# blue_pot_proto.net
KiCad netlist of a schematic drawn in EAGLE
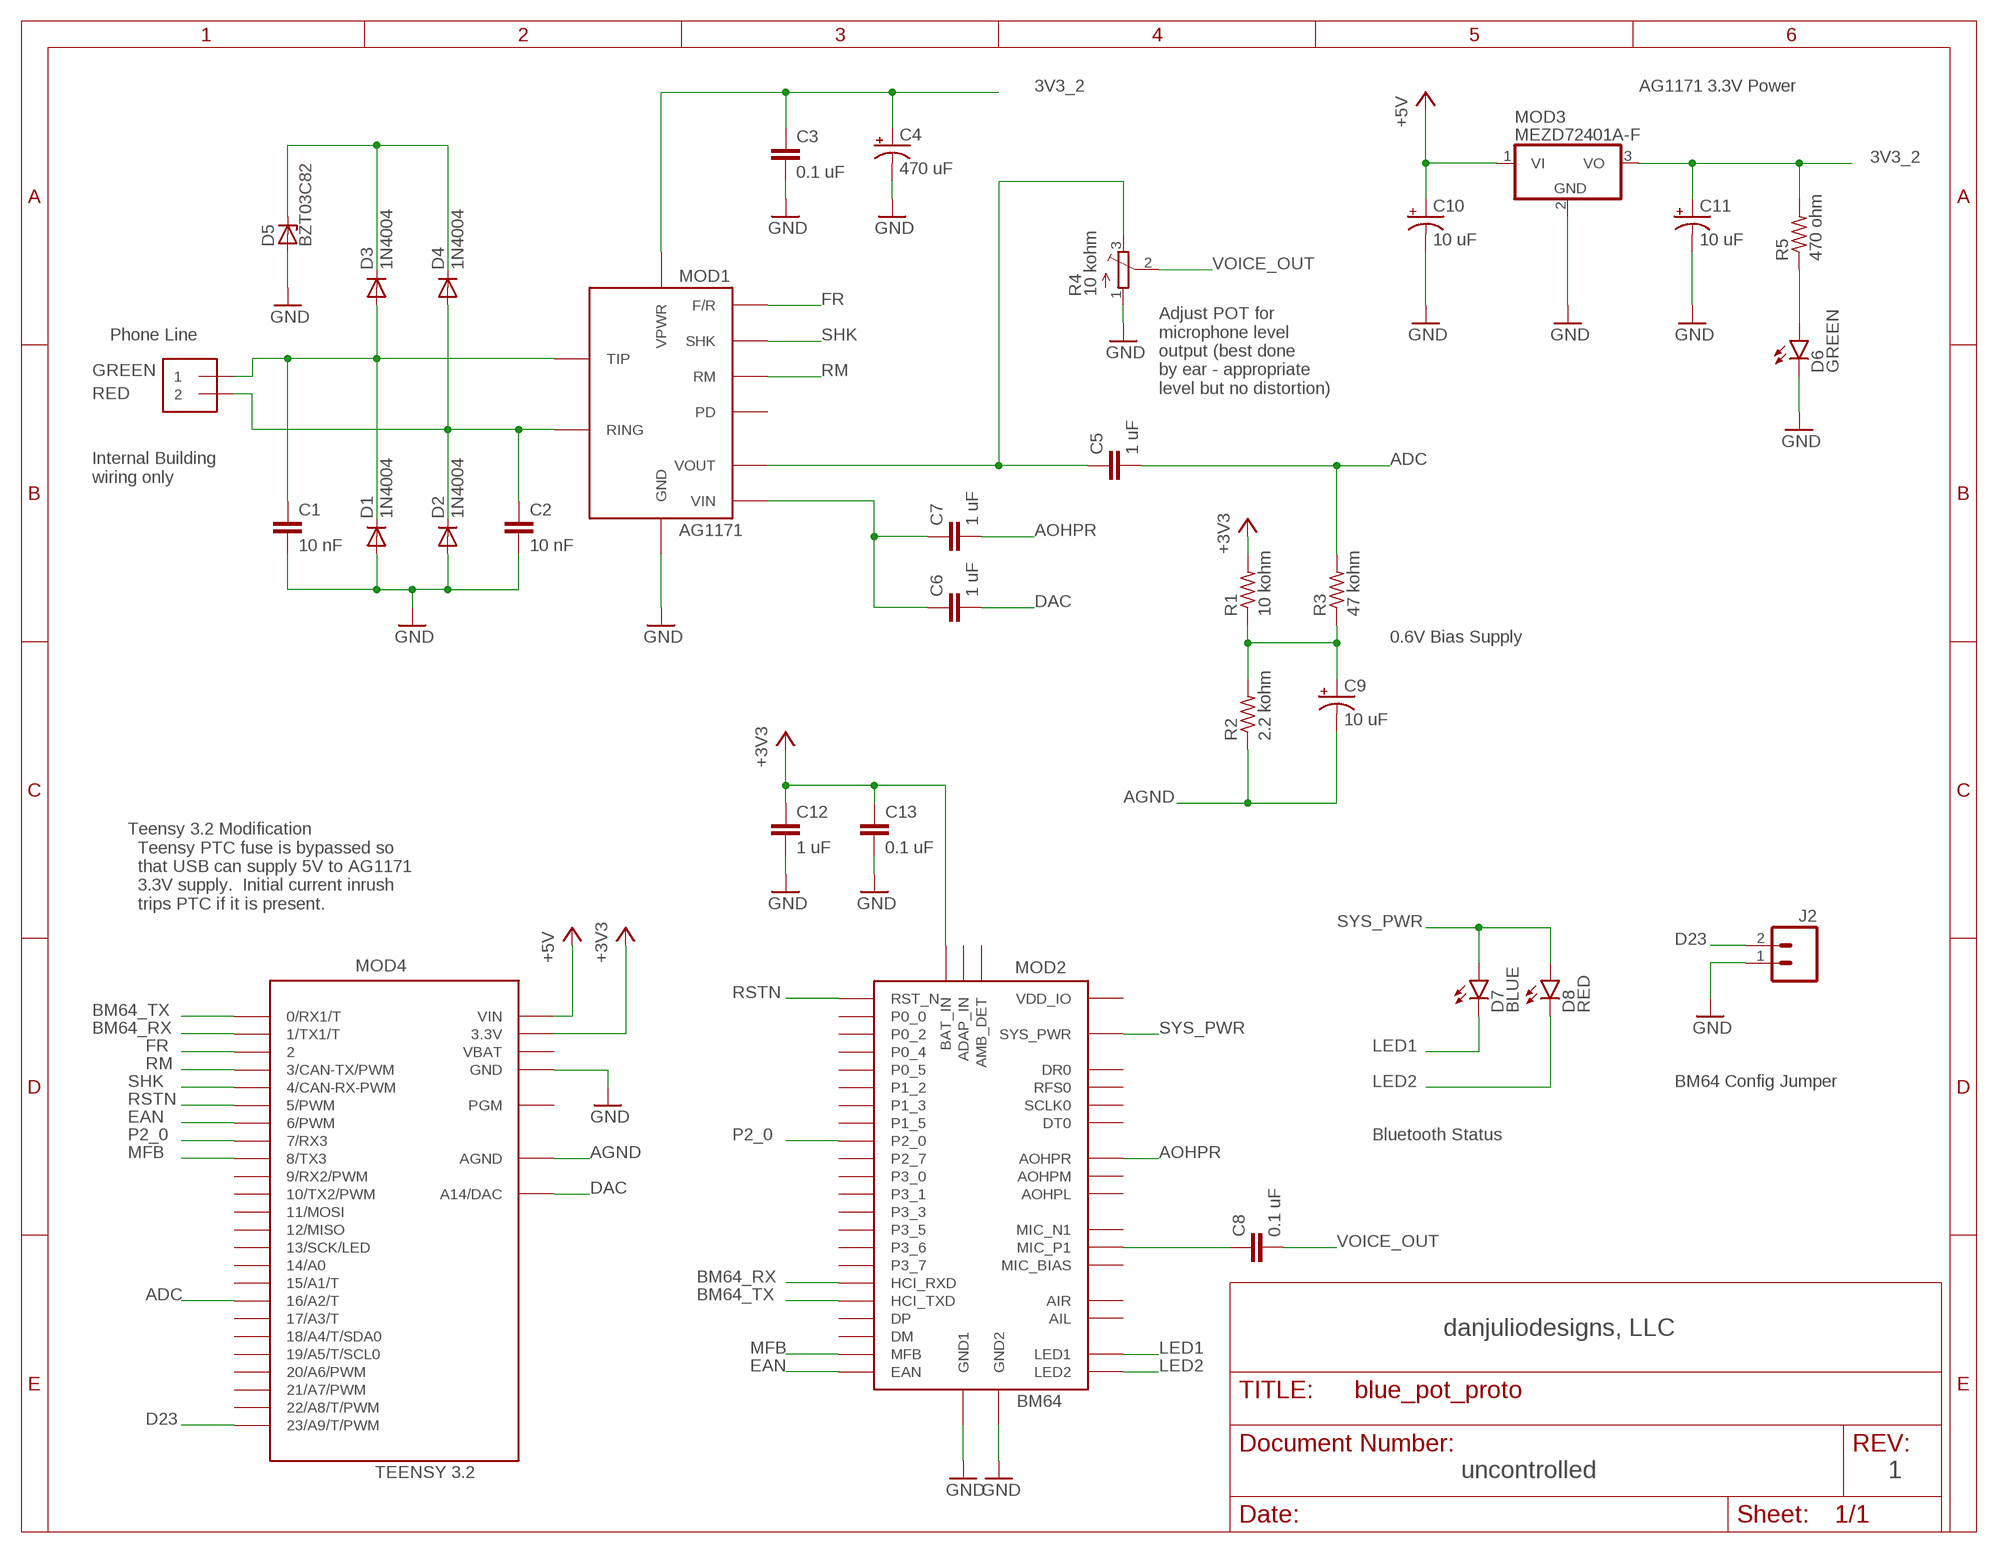
[diagram p0: schematic, sheet 1]

(export (version "E")
  (design (tool "Eeschema 10.0.6"))
  (components
    (comp (ref "C1")
      (value "10 nF")
      (footprint "eagle-import:C5B2.5")
      (libsource (lib "eagle-import") (part "C5/2.5"))
    )
    (comp (ref "C2")
      (value "10 nF")
      (footprint "eagle-import:C5B2.5")
      (libsource (lib "eagle-import") (part "C5/2.5"))
    )
    (comp (ref "C3")
      (value "0.1 uF")
      (footprint "eagle-import:C5B2.5")
      (libsource (lib "eagle-import") (part "C5/2.5"))
    )
    (comp (ref "C4")
      (value "470 uF")
      (footprint "eagle-import:TT5D10")
      (libsource (lib "eagle-import") (part "CPOL-USTT5D10"))
    )
    (comp (ref "C5")
      (value "1 uF")
      (footprint "eagle-import:C5B2.5")
      (libsource (lib "eagle-import") (part "C5/2.5"))
    )
    (comp (ref "C6")
      (value "1 uF")
      (footprint "eagle-import:C5B2.5")
      (libsource (lib "eagle-import") (part "C5/2.5"))
    )
    (comp (ref "C7")
      (value "1 uF")
      (footprint "eagle-import:C5B2.5")
      (libsource (lib "eagle-import") (part "C5/2.5"))
    )
    (comp (ref "C8")
      (value "0.1 uF")
      (footprint "eagle-import:C5B2.5")
      (libsource (lib "eagle-import") (part "C5/2.5"))
    )
    (comp (ref "C9")
      (value "10 uF")
      (footprint "eagle-import:TT2D5")
      (libsource (lib "eagle-import") (part "CPOL-USTT2D5"))
    )
    (comp (ref "C10")
      (value "10 uF")
      (footprint "eagle-import:TT2D5")
      (libsource (lib "eagle-import") (part "CPOL-USTT2D5"))
    )
    (comp (ref "C11")
      (value "10 uF")
      (footprint "eagle-import:TT2D5")
      (libsource (lib "eagle-import") (part "CPOL-USTT2D5"))
    )
    (comp (ref "C12")
      (value "1 uF")
      (footprint "eagle-import:C5B2.5")
      (libsource (lib "eagle-import") (part "C5/2.5"))
    )
    (comp (ref "C13")
      (value "0.1 uF")
      (footprint "eagle-import:C5B2.5")
      (libsource (lib "eagle-import") (part "C5/2.5"))
    )
    (comp (ref "D1")
      (value "1N4004")
      (footprint "eagle-import:DO41-10")
      (libsource (lib "eagle-import") (part "1N4004"))
    )
    (comp (ref "D2")
      (value "1N4004")
      (footprint "eagle-import:DO41-10")
      (libsource (lib "eagle-import") (part "1N4004"))
    )
    (comp (ref "D3")
      (value "1N4004")
      (footprint "eagle-import:DO41-10")
      (libsource (lib "eagle-import") (part "1N4004"))
    )
    (comp (ref "D4")
      (value "1N4004")
      (footprint "eagle-import:DO41-10")
      (libsource (lib "eagle-import") (part "1N4004"))
    )
    (comp (ref "D5")
      (value "BZT03C82")
      (footprint "eagle-import:SOD57Z10")
      (libsource (lib "eagle-import") (part "BZT03XX"))
    )
    (comp (ref "D6")
      (value "GREEN")
      (footprint "eagle-import:LED5MM")
      (libsource (lib "eagle-import") (part "LED5MM"))
    )
    (comp (ref "D7")
      (value "BLUE")
      (footprint "eagle-import:LED5MM")
      (libsource (lib "eagle-import") (part "LED5MM"))
    )
    (comp (ref "D8")
      (value "RED")
      (footprint "eagle-import:LED5MM")
      (libsource (lib "eagle-import") (part "LED5MM"))
    )
    (comp (ref "J1")
      (value "1X2-3.5MM")
      (footprint "eagle-import:1X2-3.5MM")
      (libsource (lib "eagle-import") (part "1X2-3.5MM"))
    )
    (comp (ref "J2")
      (value "M02PTH")
      (footprint "eagle-import:1X02")
      (libsource (lib "eagle-import") (part "M02PTH"))
    )
    (comp (ref "MOD1")
      (value "AG1171")
      (footprint "eagle-import:AG1171")
      (libsource (lib "eagle-import") (part "AG1171SIL"))
    )
    (comp (ref "MOD2")
      (value "BM64")
      (footprint "eagle-import:BM64")
      (libsource (lib "eagle-import") (part "BM64"))
    )
    (comp (ref "MOD3")
      (value "MEZD72401A-F")
      (footprint "eagle-import:TO220H")
      (libsource (lib "eagle-import") (part "78T05"))
    )
    (comp (ref "MOD4")
      (value "TEENSY 3.2")
      (footprint "eagle-import:TEENSY_3.0-3.2&LC_OUTER_ROW")
      (libsource (lib "eagle-import") (part "TEENSY_3.1-3.2_OUTER_ROW"))
    )
    (comp (ref "R1")
      (value "10 kohm")
      (footprint "eagle-import:0207_10")
      (libsource (lib "eagle-import") (part "R-US_0207/10"))
    )
    (comp (ref "R2")
      (value "2.2 kohm")
      (footprint "eagle-import:0207_10")
      (libsource (lib "eagle-import") (part "R-US_0207/10"))
    )
    (comp (ref "R3")
      (value "47 kohm")
      (footprint "eagle-import:0207_10")
      (libsource (lib "eagle-import") (part "R-US_0207/10"))
    )
    (comp (ref "R4")
      (value "10 kohm")
      (footprint "eagle-import:TC33X")
      (libsource (lib "eagle-import") (part "TRIMPOTTC33X"))
    )
    (comp (ref "R5")
      (value "470 ohm")
      (footprint "eagle-import:0207_10")
      (libsource (lib "eagle-import") (part "R-US_0207/10"))
    )
  )
  (nets
    (net (code "1") (name "+3V3") (class "Default")
      (node (ref "C12") (pin "1") (pinfunction "1_1") (pintype "passive"))
      (node (ref "C13") (pin "1") (pinfunction "1_1") (pintype "passive"))
      (node (ref "MOD2") (pin "22") (pinfunction "BAT_IN_22") (pintype "power_in"))
      (node (ref "MOD4") (pin "3.3V") (pinfunction "3.3V_3.3V") (pintype "power_in"))
      (node (ref "MOD4") (pin "3.3V1") (pinfunction "3.3V_3.3V1") (pintype "power_in"))
      (node (ref "R1") (pin "2") (pinfunction "2_2") (pintype "passive"))
    )
    (net (code "2") (name "+5V") (class "Default")
      (node (ref "C10") (pin "+") (pinfunction "+_+") (pintype "passive"))
      (node (ref "MOD3") (pin "1") (pinfunction "VI_1") (pintype "input"))
      (node (ref "MOD4") (pin "VIN") (pinfunction "VIN_VIN") (pintype "power_in"))
    )
    (net (code "3") (name "/3V3_2") (class "Default")
      (node (ref "C11") (pin "+") (pinfunction "+_+") (pintype "passive"))
      (node (ref "C3") (pin "1") (pinfunction "1_1") (pintype "passive"))
      (node (ref "C4") (pin "+") (pinfunction "+_+") (pintype "passive"))
      (node (ref "MOD1") (pin "P$13") (pinfunction "VPWR_P$13") (pintype "power_in"))
      (node (ref "MOD3") (pin "3") (pinfunction "VO_3") (pintype "passive"))
    )
    (net (code "4") (name "/ADAP_IN") (class "Default")
      (node (ref "MOD2") (pin "23") (pinfunction "ADAP_IN_23") (pintype "power_in"))
    )
    (net (code "5") (name "/ADC") (class "Default")
      (node (ref "C5") (pin "2") (pinfunction "2_2") (pintype "passive"))
      (node (ref "MOD4") (pin "16/A2") (pinfunction "16/A2/T_16/A2") (pintype "bidirectional"))
      (node (ref "R3") (pin "2") (pinfunction "2_2") (pintype "passive"))
    )
    (net (code "6") (name "/AGND") (class "Default")
      (node (ref "C9") (pin "-") (pinfunction "-_-") (pintype "passive"))
      (node (ref "MOD4") (pin "AGND") (pinfunction "AGND_AGND") (pintype "power_in"))
      (node (ref "R2") (pin "1") (pinfunction "1_1") (pintype "passive"))
    )
    (net (code "7") (name "/AOHPR") (class "Default")
      (node (ref "C7") (pin "2") (pinfunction "2_2") (pintype "passive"))
      (node (ref "MOD2") (pin "5") (pinfunction "AOHPR_5") (pintype "passive"))
    )
    (net (code "8") (name "/BM64_RX") (class "Default")
      (node (ref "MOD2") (pin "19") (pinfunction "HCI_RXD_19") (pintype "input"))
      (node (ref "MOD4") (pin "1") (pinfunction "1/TX1/T_1") (pintype "bidirectional"))
    )
    (net (code "9") (name "/BM64_TX") (class "Default")
      (node (ref "MOD2") (pin "20") (pinfunction "HCI_TXD_20") (pintype "output"))
      (node (ref "MOD4") (pin "0") (pinfunction "0/RX1/T_0") (pintype "bidirectional"))
    )
    (net (code "10") (name "/D23") (class "Default")
      (node (ref "J2") (pin "2") (pinfunction "2_2") (pintype "passive"))
      (node (ref "MOD4") (pin "23/A9") (pinfunction "23/A9/T/PWM_23/A9") (pintype "bidirectional"))
    )
    (net (code "11") (name "/DAC") (class "Default")
      (node (ref "C6") (pin "2") (pinfunction "2_2") (pintype "passive"))
      (node (ref "MOD4") (pin "RESET/DAC") (pinfunction "A14/DAC_RESET/DAC") (pintype "bidirectional"))
    )
    (net (code "12") (name "/EAN") (class "Default")
      (node (ref "MOD2") (pin "32") (pinfunction "EAN_32") (pintype "input"))
      (node (ref "MOD4") (pin "6") (pinfunction "6/PWM_6") (pintype "bidirectional"))
    )
    (net (code "13") (name "/FR") (class "Default")
      (node (ref "MOD1") (pin "P$3") (pinfunction "F/R_P$3") (pintype "input"))
      (node (ref "MOD4") (pin "2") (pinfunction "2_2") (pintype "bidirectional"))
    )
    (net (code "14") (name "/LED1") (class "Default")
      (node (ref "D7") (pin "K") (pinfunction "C_K") (pintype "passive"))
      (node (ref "MOD2") (pin "28") (pinfunction "LED1_28") (pintype "output"))
    )
    (net (code "15") (name "/LED2") (class "Default")
      (node (ref "D8") (pin "K") (pinfunction "C_K") (pintype "passive"))
      (node (ref "MOD2") (pin "27") (pinfunction "LED2_27") (pintype "output"))
    )
    (net (code "16") (name "/MFB") (class "Default")
      (node (ref "MOD2") (pin "26") (pinfunction "MFB_26") (pintype "input"))
      (node (ref "MOD4") (pin "8") (pinfunction "8/TX3_8") (pintype "bidirectional"))
    )
    (net (code "17") (name "/MIC_BIAS") (class "Default")
      (node (ref "MOD2") (pin "10") (pinfunction "MIC_BIAS_10") (pintype "power_in"))
    )
    (net (code "18") (name "/P2_0") (class "Default")
      (node (ref "MOD2") (pin "41") (pinfunction "P2_0_41") (pintype "bidirectional"))
      (node (ref "MOD4") (pin "7") (pinfunction "7/RX3_7") (pintype "bidirectional"))
    )
    (net (code "19") (name "/RM") (class "Default")
      (node (ref "MOD1") (pin "P$4") (pinfunction "RM_P$4") (pintype "input"))
      (node (ref "MOD4") (pin "3") (pinfunction "3/CAN-TX/PWM_3") (pintype "bidirectional"))
    )
    (net (code "20") (name "/RSTN") (class "Default")
      (node (ref "MOD2") (pin "13") (pinfunction "RST_N_13") (pintype "input"))
      (node (ref "MOD4") (pin "5") (pinfunction "5/PWM_5") (pintype "bidirectional"))
    )
    (net (code "21") (name "/SHK") (class "Default")
      (node (ref "MOD1") (pin "P$5") (pinfunction "SHK_P$5") (pintype "output"))
      (node (ref "MOD4") (pin "4") (pinfunction "4/CAN-RX-PWM_4") (pintype "bidirectional"))
    )
    (net (code "22") (name "/SYS_PWR") (class "Default")
      (node (ref "D7") (pin "A") (pinfunction "A_A") (pintype "passive"))
      (node (ref "D8") (pin "A") (pinfunction "A_A") (pintype "passive"))
      (node (ref "MOD2") (pin "24") (pinfunction "SYS_PWR_24") (pintype "power_in"))
    )
    (net (code "23") (name "/VBAT") (class "Default")
      (node (ref "MOD4") (pin "VBAT") (pinfunction "VBAT_VBAT") (pintype "power_in"))
    )
    (net (code "24") (name "/VDD_IO") (class "Default")
      (node (ref "MOD2") (pin "21") (pinfunction "VDD_IO_21") (pintype "power_in"))
    )
    (net (code "25") (name "/VOICE_OUT") (class "Default")
      (node (ref "C8") (pin "2") (pinfunction "2_2") (pintype "passive"))
      (node (ref "R4") (pin "2") (pinfunction "S_2") (pintype "passive"))
    )
    (net (code "26") (name "GND") (class "Default")
      (node (ref "C1") (pin "2") (pinfunction "2_2") (pintype "passive"))
      (node (ref "C10") (pin "-") (pinfunction "-_-") (pintype "passive"))
      (node (ref "C11") (pin "-") (pinfunction "-_-") (pintype "passive"))
      (node (ref "C12") (pin "2") (pinfunction "2_2") (pintype "passive"))
      (node (ref "C13") (pin "2") (pinfunction "2_2") (pintype "passive"))
      (node (ref "C2") (pin "2") (pinfunction "2_2") (pintype "passive"))
      (node (ref "C3") (pin "2") (pinfunction "2_2") (pintype "passive"))
      (node (ref "C4") (pin "-") (pinfunction "-_-") (pintype "passive"))
      (node (ref "D1") (pin "A") (pinfunction "A_A") (pintype "passive"))
      (node (ref "D2") (pin "A") (pinfunction "A_A") (pintype "passive"))
      (node (ref "D5") (pin "A") (pinfunction "A_A") (pintype "passive"))
      (node (ref "D6") (pin "K") (pinfunction "C_K") (pintype "passive"))
      (node (ref "J2") (pin "1") (pinfunction "1_1") (pintype "passive"))
      (node (ref "MOD1") (pin "P$12") (pinfunction "GND_P$12") (pintype "power_in"))
      (node (ref "MOD2") (pin "14") (pinfunction "GND1_14") (pintype "power_in"))
      (node (ref "MOD2") (pin "43") (pinfunction "GND2_43") (pintype "power_in"))
      (node (ref "MOD3") (pin "2") (pinfunction "GND_2") (pintype "passive"))
      (node (ref "MOD4") (pin "GND") (pinfunction "GND_GND") (pintype "power_in"))
      (node (ref "MOD4") (pin "GND1") (pinfunction "GND_GND1") (pintype "power_in"))
      (node (ref "R4") (pin "1") (pinfunction "A_1") (pintype "passive"))
    )
    (net (code "27") (name "Net-(C9-Pad+)") (class "Default")
      (node (ref "C9") (pin "+") (pinfunction "+_+") (pintype "passive"))
      (node (ref "R1") (pin "1") (pinfunction "1_1") (pintype "passive"))
      (node (ref "R2") (pin "2") (pinfunction "2_2") (pintype "passive"))
      (node (ref "R3") (pin "1") (pinfunction "1_1") (pintype "passive"))
    )
    (net (code "28") (name "Net-(D3-PadC)") (class "Default")
      (node (ref "D3") (pin "C") (pinfunction "C_C") (pintype "passive"))
      (node (ref "D4") (pin "C") (pinfunction "C_C") (pintype "passive"))
      (node (ref "D5") (pin "C") (pinfunction "C_C") (pintype "passive"))
    )
    (net (code "29") (name "Net-(MOD1-RING)") (class "Default")
      (node (ref "C2") (pin "1") (pinfunction "1_1") (pintype "passive"))
      (node (ref "D2") (pin "C") (pinfunction "C_C") (pintype "passive"))
      (node (ref "D4") (pin "A") (pinfunction "A_A") (pintype "passive"))
      (node (ref "J1") (pin "2") (pinfunction "2_2") (pintype "passive"))
      (node (ref "MOD1") (pin "P$1") (pinfunction "RING_P$1") (pintype "bidirectional"))
    )
    (net (code "30") (name "Net-(MOD1-TIP)") (class "Default")
      (node (ref "C1") (pin "1") (pinfunction "1_1") (pintype "passive"))
      (node (ref "D1") (pin "C") (pinfunction "C_C") (pintype "passive"))
      (node (ref "D3") (pin "A") (pinfunction "A_A") (pintype "passive"))
      (node (ref "J1") (pin "1") (pinfunction "1_1") (pintype "passive"))
      (node (ref "MOD1") (pin "P$2") (pinfunction "TIP_P$2") (pintype "bidirectional"))
    )
    (net (code "31") (name "Net-(MOD1-VIN)") (class "Default")
      (node (ref "C6") (pin "1") (pinfunction "1_1") (pintype "passive"))
      (node (ref "C7") (pin "1") (pinfunction "1_1") (pintype "passive"))
      (node (ref "MOD1") (pin "P$9") (pinfunction "VIN_P$9") (pintype "input"))
    )
    (net (code "32") (name "Net-(MOD1-VOUT)") (class "Default")
      (node (ref "C5") (pin "1") (pinfunction "1_1") (pintype "passive"))
      (node (ref "MOD1") (pin "P$10") (pinfunction "VOUT_P$10") (pintype "output"))
      (node (ref "R4") (pin "3") (pinfunction "E_3") (pintype "passive"))
    )
    (net (code "33") (name "Net-(MOD2-MIC_P1)") (class "Default")
      (node (ref "C8") (pin "1") (pinfunction "1_1") (pintype "passive"))
      (node (ref "MOD2") (pin "9") (pinfunction "MIC_P1_9") (pintype "passive"))
    )
    (net (code "34") (name "unconnected-(D6-PadA)") (class "Default")
      (node (ref "D6") (pin "A") (pinfunction "A_A") (pintype "passive"))
    )
    (net (code "35") (name "unconnected-(MOD1-PD-PadP$14)") (class "Default")
      (node (ref "MOD1") (pin "P$14") (pinfunction "PD_P$14") (pintype "input"))
    )
    (net (code "36") (name "unconnected-(MOD2-AIL-Pad12)") (class "Default")
      (node (ref "MOD2") (pin "12") (pinfunction "AIL_12") (pintype "passive"))
    )
    (net (code "37") (name "unconnected-(MOD2-AIR-Pad11)") (class "Default")
      (node (ref "MOD2") (pin "11") (pinfunction "AIR_11") (pintype "passive"))
    )
    (net (code "38") (name "unconnected-(MOD2-AMB_DET-Pad25)") (class "Default")
      (node (ref "MOD2") (pin "25") (pinfunction "AMB_DET_25") (pintype "passive"))
    )
    (net (code "39") (name "unconnected-(MOD2-AOHPL-Pad7)") (class "Default")
      (node (ref "MOD2") (pin "7") (pinfunction "AOHPL_7") (pintype "passive"))
    )
    (net (code "40") (name "unconnected-(MOD2-AOHPM-Pad6)") (class "Default")
      (node (ref "MOD2") (pin "6") (pinfunction "AOHPM_6") (pintype "passive"))
    )
    (net (code "41") (name "unconnected-(MOD2-DM-Pad33)") (class "Default")
      (node (ref "MOD2") (pin "33") (pinfunction "DM_33") (pintype "bidirectional"))
    )
    (net (code "42") (name "unconnected-(MOD2-DP-Pad34)") (class "Default")
      (node (ref "MOD2") (pin "34") (pinfunction "DP_34") (pintype "bidirectional"))
    )
    (net (code "43") (name "unconnected-(MOD2-DR0-Pad1)") (class "Default")
      (node (ref "MOD2") (pin "1") (pinfunction "DR0_1") (pintype "bidirectional"))
    )
    (net (code "44") (name "unconnected-(MOD2-DT0-Pad4)") (class "Default")
      (node (ref "MOD2") (pin "4") (pinfunction "DT0_4") (pintype "bidirectional"))
    )
    (net (code "45") (name "unconnected-(MOD2-MIC_N1-Pad8)") (class "Default")
      (node (ref "MOD2") (pin "8") (pinfunction "MIC_N1_8") (pintype "passive"))
    )
    (net (code "46") (name "unconnected-(MOD2-P0_0-Pad31)") (class "Default")
      (node (ref "MOD2") (pin "31") (pinfunction "P0_0_31") (pintype "bidirectional"))
    )
    (net (code "47") (name "unconnected-(MOD2-P0_2-Pad40)") (class "Default")
      (node (ref "MOD2") (pin "40") (pinfunction "P0_2_40") (pintype "bidirectional"))
    )
    (net (code "48") (name "unconnected-(MOD2-P0_4-Pad17)") (class "Default")
      (node (ref "MOD2") (pin "17") (pinfunction "P0_4_17") (pintype "bidirectional"))
    )
    (net (code "49") (name "unconnected-(MOD2-P0_5-Pad35)") (class "Default")
      (node (ref "MOD2") (pin "35") (pinfunction "P0_5_35") (pintype "bidirectional"))
    )
    (net (code "50") (name "unconnected-(MOD2-P1_2-Pad15)") (class "Default")
      (node (ref "MOD2") (pin "15") (pinfunction "P1_2_15") (pintype "bidirectional"))
    )
    (net (code "51") (name "unconnected-(MOD2-P1_3-Pad16)") (class "Default")
      (node (ref "MOD2") (pin "16") (pinfunction "P1_3_16") (pintype "bidirectional"))
    )
    (net (code "52") (name "unconnected-(MOD2-P1_5-Pad18)") (class "Default")
      (node (ref "MOD2") (pin "18") (pinfunction "P1_5_18") (pintype "bidirectional"))
    )
    (net (code "53") (name "unconnected-(MOD2-P2_7-Pad42)") (class "Default")
      (node (ref "MOD2") (pin "42") (pinfunction "P2_7_42") (pintype "bidirectional"))
    )
    (net (code "54") (name "unconnected-(MOD2-P3_0-Pad36)") (class "Default")
      (node (ref "MOD2") (pin "36") (pinfunction "P3_0_36") (pintype "bidirectional"))
    )
    (net (code "55") (name "unconnected-(MOD2-P3_1-Pad37)") (class "Default")
      (node (ref "MOD2") (pin "37") (pinfunction "P3_1_37") (pintype "bidirectional"))
    )
    (net (code "56") (name "unconnected-(MOD2-P3_3-Pad38)") (class "Default")
      (node (ref "MOD2") (pin "38") (pinfunction "P3_3_38") (pintype "bidirectional"))
    )
    (net (code "57") (name "unconnected-(MOD2-P3_5-Pad30)") (class "Default")
      (node (ref "MOD2") (pin "30") (pinfunction "P3_5_30") (pintype "bidirectional"))
    )
    (net (code "58") (name "unconnected-(MOD2-P3_6-Pad39)") (class "Default")
      (node (ref "MOD2") (pin "39") (pinfunction "P3_6_39") (pintype "bidirectional"))
    )
    (net (code "59") (name "unconnected-(MOD2-P3_7-Pad29)") (class "Default")
      (node (ref "MOD2") (pin "29") (pinfunction "P3_7_29") (pintype "bidirectional"))
    )
    (net (code "60") (name "unconnected-(MOD2-RFS0-Pad2)") (class "Default")
      (node (ref "MOD2") (pin "2") (pinfunction "RFS0_2") (pintype "bidirectional"))
    )
    (net (code "61") (name "unconnected-(MOD2-SCLK0-Pad3)") (class "Default")
      (node (ref "MOD2") (pin "3") (pinfunction "SCLK0_3") (pintype "bidirectional"))
    )
    (net (code "62") (name "unconnected-(MOD4-9{slash}RX2{slash}PWM-Pad9)") (class "Default")
      (node (ref "MOD4") (pin "9") (pinfunction "9/RX2/PWM_9") (pintype "bidirectional"))
    )
    (net (code "63") (name "unconnected-(MOD4-10{slash}TX2{slash}PWM-Pad10)") (class "Default")
      (node (ref "MOD4") (pin "10") (pinfunction "10/TX2/PWM_10") (pintype "bidirectional"))
    )
    (net (code "64") (name "unconnected-(MOD4-11{slash}MOSI-Pad11)") (class "Default")
      (node (ref "MOD4") (pin "11") (pinfunction "11/MOSI_11") (pintype "bidirectional"))
    )
    (net (code "65") (name "unconnected-(MOD4-12{slash}MISO-Pad12)") (class "Default")
      (node (ref "MOD4") (pin "12") (pinfunction "12/MISO_12") (pintype "bidirectional"))
    )
    (net (code "66") (name "unconnected-(MOD4-13{slash}SCK{slash}LED-Pad13)") (class "Default")
      (node (ref "MOD4") (pin "13") (pinfunction "13/SCK/LED_13") (pintype "bidirectional"))
    )
    (net (code "67") (name "unconnected-(MOD4-15{slash}A1{slash}T-Pad15{slash}A1)") (class "Default")
      (node (ref "MOD4") (pin "15/A1") (pinfunction "15/A1/T_15/A1") (pintype "bidirectional"))
    )
    (net (code "68") (name "unconnected-(MOD4-17{slash}A3{slash}T-Pad17{slash}A3)") (class "Default")
      (node (ref "MOD4") (pin "17/A3") (pinfunction "17/A3/T_17/A3") (pintype "bidirectional"))
    )
    (net (code "69") (name "unconnected-(MOD4-18{slash}A4{slash}T{slash}SDA0-Pad18{slash}A4)") (class "Default")
      (node (ref "MOD4") (pin "18/A4") (pinfunction "18/A4/T/SDA0_18/A4") (pintype "bidirectional"))
    )
    (net (code "70") (name "unconnected-(MOD4-19{slash}A5{slash}T{slash}SCL0-Pad19{slash}A5)") (class "Default")
      (node (ref "MOD4") (pin "19/A5") (pinfunction "19/A5/T/SCL0_19/A5") (pintype "bidirectional"))
    )
    (net (code "71") (name "unconnected-(MOD4-20{slash}A6{slash}PWM-Pad20{slash}A6)") (class "Default")
      (node (ref "MOD4") (pin "20/A6") (pinfunction "20/A6/PWM_20/A6") (pintype "bidirectional"))
    )
    (net (code "72") (name "unconnected-(MOD4-21{slash}A7{slash}PWM-Pad21{slash}A7)") (class "Default")
      (node (ref "MOD4") (pin "21/A7") (pinfunction "21/A7/PWM_21/A7") (pintype "bidirectional"))
    )
    (net (code "73") (name "unconnected-(MOD4-22{slash}A8{slash}T{slash}PWM-Pad22{slash}A8)") (class "Default")
      (node (ref "MOD4") (pin "22/A8") (pinfunction "22/A8/T/PWM_22/A8") (pintype "bidirectional"))
    )
    (net (code "74") (name "unconnected-(MOD4-Pad14{slash}A0)") (class "Default")
      (node (ref "MOD4") (pin "14/A0") (pinfunction "14/A0_14/A0") (pintype "bidirectional"))
    )
    (net (code "75") (name "unconnected-(MOD4-PadPGM)") (class "Default")
      (node (ref "MOD4") (pin "PGM") (pinfunction "PGM_PGM") (pintype "bidirectional"))
    )
    (net (code "76") (name "unconnected-(R5-Pad1)") (class "Default")
      (node (ref "R5") (pin "1") (pinfunction "1_1") (pintype "passive"))
    )
    (net (code "77") (name "unconnected-(R5-Pad2)") (class "Default")
      (node (ref "R5") (pin "2") (pinfunction "2_2") (pintype "passive"))
    )
  )
)
